# dev1.net
KiCad netlist of a schematic drawn in Altium Designer
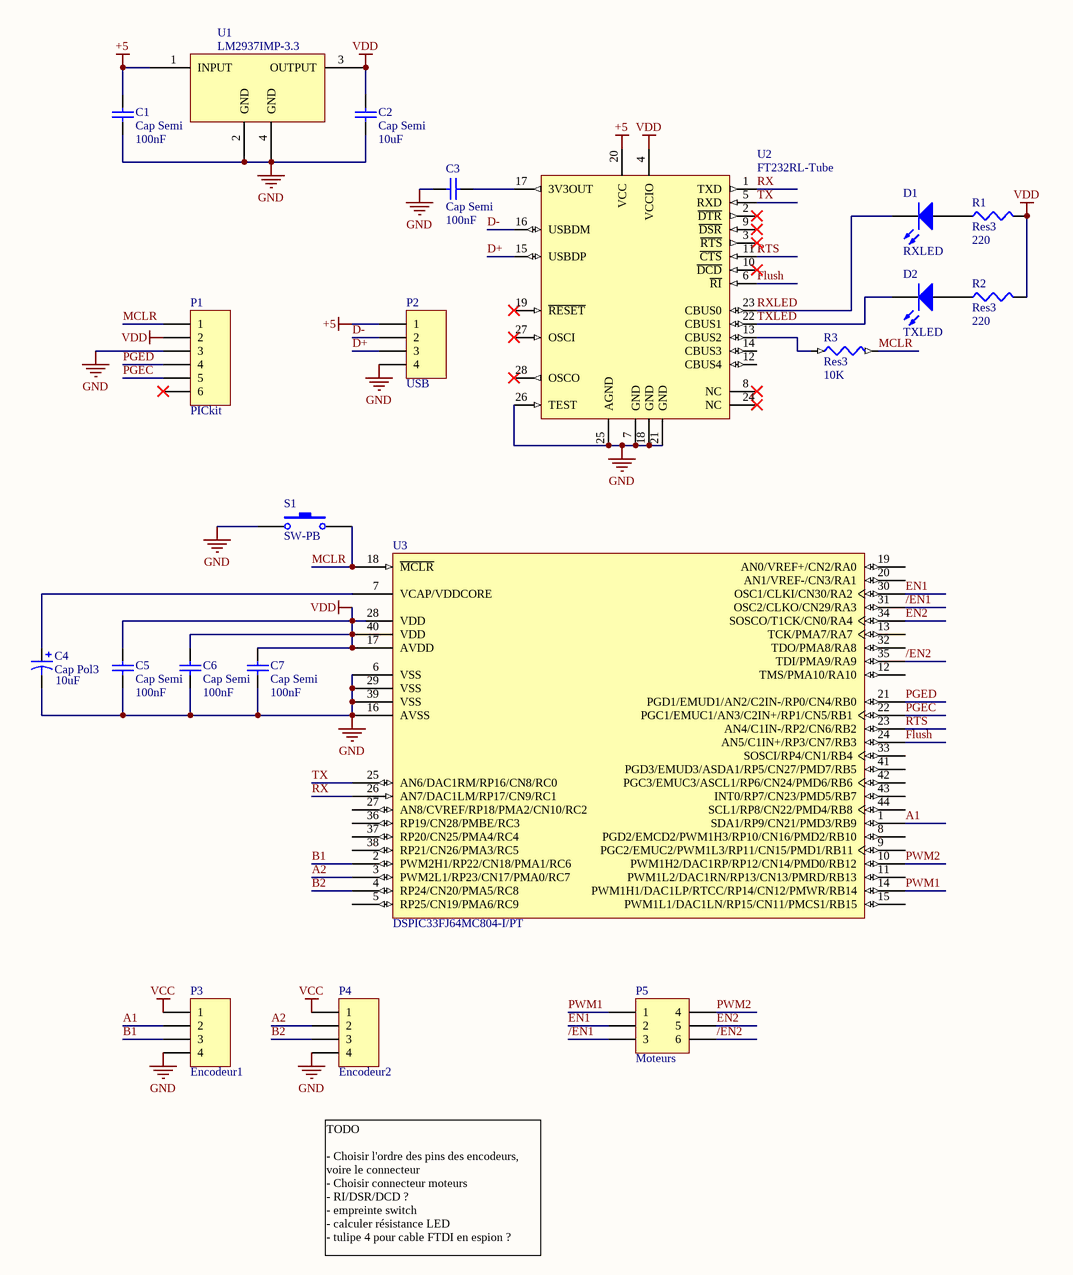
[diagram p0: dev1.SchDoc]

(export (version "E")
  (design (tool "Eeschema 10.0.6"))
  (components
    (comp (ref "C1")
      (value "Cap Semi")
      (footprint "C1206")
      (description "Capacitor (Semiconductor SIM Model)")
      (fields (field (name "ALTIUM_VALUE") "100nF") (field (name "PUBLISHER") "Altium Limited"))
      (libsource (lib "Miscellaneous Devices") (part "Cap Semi"))
    )
    (comp (ref "C2")
      (value "Cap Semi")
      (footprint "C1206")
      (description "Capacitor (Semiconductor SIM Model)")
      (fields (field (name "ALTIUM_VALUE") "10uF") (field (name "PUBLISHER") "Altium Limited"))
      (libsource (lib "Miscellaneous Devices") (part "Cap Semi"))
    )
    (comp (ref "C3")
      (value "Cap Semi")
      (footprint "C1206")
      (description "Capacitor (Semiconductor SIM Model)")
      (fields (field (name "ALTIUM_VALUE") "100nF") (field (name "PUBLISHER") "Altium Limited"))
      (libsource (lib "Miscellaneous Devices") (part "Cap Semi"))
    )
    (comp (ref "C4")
      (value "Cap Pol3")
      (footprint "C0805")
      (description "Polarized Capacitor (Surface Mount)")
      (fields (field (name "ALTIUM_VALUE") "10uF") (field (name "PUBLISHER") "Altium Limited"))
      (libsource (lib "Miscellaneous Devices") (part "Cap Pol3"))
    )
    (comp (ref "C5")
      (value "Cap Semi")
      (footprint "C1206")
      (description "Capacitor (Semiconductor SIM Model)")
      (fields (field (name "ALTIUM_VALUE") "100nF") (field (name "PUBLISHER") "Altium Limited"))
      (libsource (lib "Miscellaneous Devices") (part "Cap Semi"))
    )
    (comp (ref "C6")
      (value "Cap Semi")
      (footprint "C1206")
      (description "Capacitor (Semiconductor SIM Model)")
      (fields (field (name "ALTIUM_VALUE") "100nF") (field (name "PUBLISHER") "Altium Limited"))
      (libsource (lib "Miscellaneous Devices") (part "Cap Semi"))
    )
    (comp (ref "C7")
      (value "Cap Semi")
      (footprint "C1206")
      (description "Capacitor (Semiconductor SIM Model)")
      (fields (field (name "ALTIUM_VALUE") "100nF") (field (name "PUBLISHER") "Altium Limited"))
      (libsource (lib "Miscellaneous Devices") (part "Cap Semi"))
    )
    (comp (ref "D1")
      (value "RXLED")
      (footprint "3.2X1.6X1.1")
      (description "Typical RED, GREEN, YELLOW, AMBER GaAs LED")
      (fields (field (name "PUBLISHER") "Altium Limited"))
      (libsource (lib "Miscellaneous Devices") (part "LED2"))
    )
    (comp (ref "D2")
      (value "TXLED")
      (footprint "3.2X1.6X1.1")
      (description "Typical RED, GREEN, YELLOW, AMBER GaAs LED")
      (fields (field (name "PUBLISHER") "Altium Limited"))
      (libsource (lib "Miscellaneous Devices") (part "LED2"))
    )
    (comp (ref "P1")
      (value "PICkit")
      (footprint "HDR1X6H")
      (description "Header, 6-Pin, Right Angle")
      (fields (field (name "PUBLISHER") "Altium Limited"))
      (libsource (lib "Miscellaneous Connectors") (part "Header 6H"))
    )
    (comp (ref "P2")
      (value "USB")
      (footprint "HDR1X4")
      (description "Header, 4-Pin")
      (fields (field (name "PUBLISHER") "Altium Limited"))
      (libsource (lib "Miscellaneous Connectors") (part "Header 4"))
    )
    (comp (ref "P3")
      (value "Encodeur1")
      (footprint "HDR1X4")
      (description "Header, 4-Pin")
      (fields (field (name "PUBLISHER") "Altium Limited"))
      (libsource (lib "Miscellaneous Connectors") (part "Header 4"))
    )
    (comp (ref "P4")
      (value "Encodeur2")
      (footprint "HDR1X4")
      (description "Header, 4-Pin")
      (fields (field (name "PUBLISHER") "Altium Limited"))
      (libsource (lib "Miscellaneous Connectors") (part "Header 4"))
    )
    (comp (ref "P5")
      (value "Moteurs")
      (footprint "HDR2X3_CEN")
      (description "Header, 3-Pin, Dual row")
      (fields (field (name "PUBLISHER") "Altium Limited"))
      (libsource (lib "Miscellaneous Connectors") (part "Header 3X2A"))
    )
    (comp (ref "R1")
      (value "Res3")
      (footprint "J1-0603")
      (description "Resistor")
      (fields (field (name "ALTIUM_VALUE") "220") (field (name "PUBLISHER") "Altium Limited"))
      (libsource (lib "Miscellaneous Devices") (part "Res3"))
    )
    (comp (ref "R2")
      (value "Res3")
      (footprint "J1-0603")
      (description "Resistor")
      (fields (field (name "ALTIUM_VALUE") "220") (field (name "PUBLISHER") "Altium Limited"))
      (libsource (lib "Miscellaneous Devices") (part "Res3"))
    )
    (comp (ref "R3")
      (value "Res3")
      (footprint "J1-0603")
      (description "Resistor")
      (fields (field (name "ALTIUM_VALUE") "10K") (field (name "PUBLISHER") "Altium Limited"))
      (libsource (lib "Miscellaneous Devices") (part "Res3"))
    )
    (comp (ref "S1")
      (value "SW-PB")
      (footprint "SPST-2")
      (description "Switch")
      (fields (field (name "PUBLISHER") "Altium Limited"))
      (libsource (lib "Miscellaneous Devices") (part "SW-PB"))
    )
    (comp (ref "U1")
      (value "LM2937IMP-3.3")
      (description "500 mA Low Dropout Regulator")
      (libsource (lib "7Robot") (part "LM2937IMP-3.3"))
    )
    (comp (ref "U2")
      (value "FT232RL-Tube")
      (footprint "SSOP-28_N")
      (description "USB UART Asynchronous Serial Data Transfer Chip, SSOP-28, Tube")
      (fields (field (name "PUBLISHER") "Altium Limited"))
      (libsource (lib "FTDI Communication UART") (part "FT232RL-Tube"))
    )
    (comp (ref "U3")
      (value "DSPIC33FJ64MC804-I/PT")
      (footprint "TQFP-PT44_N")
      (fields (field (name "PUBLISHER") "Altium Limited"))
      (libsource (lib "Microchip DSC 16-Bit dsPIC33F") (part "DSPIC33FJ64MC804-I/PT"))
    )
  )
  (nets
    (net (code "1") (name "+5") (class "Default")
      (node (ref "C1") (pin "1") (pinfunction "1_1") (pintype "passive"))
      (node (ref "P2") (pin "1") (pinfunction "1_1") (pintype "passive"))
      (node (ref "U1") (pin "1") (pinfunction "INPUT_1") (pintype "power_in"))
      (node (ref "U2") (pin "20") (pinfunction "VCC_20") (pintype "power_in"))
    )
    (net (code "2") (name "/A1") (class "Default")
      (node (ref "P3") (pin "2") (pinfunction "2_2") (pintype "passive"))
      (node (ref "U3") (pin "1") (pinfunction "SDA1/RP9/CN21/PMD3/RB9_1") (pintype "bidirectional"))
    )
    (net (code "3") (name "/A2") (class "Default")
      (node (ref "P4") (pin "2") (pinfunction "2_2") (pintype "passive"))
      (node (ref "U3") (pin "3") (pinfunction "PWM2L1/RP23/CN17/PMA0/RC7_3") (pintype "bidirectional"))
    )
    (net (code "4") (name "/B1") (class "Default")
      (node (ref "P3") (pin "3") (pinfunction "3_3") (pintype "passive"))
      (node (ref "U3") (pin "2") (pinfunction "PWM2H1/RP22/CN18/PMA1/RC6_2") (pintype "bidirectional"))
    )
    (net (code "5") (name "/B2") (class "Default")
      (node (ref "P4") (pin "3") (pinfunction "3_3") (pintype "passive"))
      (node (ref "U3") (pin "4") (pinfunction "RP24/CN20/PMA5/RC8_4") (pintype "bidirectional"))
    )
    (net (code "6") (name "/D+") (class "Default")
      (node (ref "P2") (pin "3") (pinfunction "3_3") (pintype "passive"))
      (node (ref "U2") (pin "15") (pinfunction "USBDP_15") (pintype "bidirectional"))
    )
    (net (code "7") (name "/D-") (class "Default")
      (node (ref "P2") (pin "2") (pinfunction "2_2") (pintype "passive"))
      (node (ref "U2") (pin "16") (pinfunction "USBDM_16") (pintype "bidirectional"))
    )
    (net (code "8") (name "/EN1") (class "Default")
      (node (ref "P5") (pin "2") (pinfunction "2_2") (pintype "passive"))
      (node (ref "U3") (pin "30") (pinfunction "OSC1/CLKI/CN30/RA2_30") (pintype "bidirectional"))
    )
    (net (code "9") (name "/EN2") (class "Default")
      (node (ref "P5") (pin "5") (pinfunction "5_5") (pintype "passive"))
      (node (ref "U3") (pin "34") (pinfunction "SOSCO/T1CK/CN0/RA4_34") (pintype "bidirectional"))
    )
    (net (code "10") (name "/Flush") (class "Default")
      (node (ref "U2") (pin "6") (pinfunction "~{RI}_6") (pintype "input"))
      (node (ref "U3") (pin "24") (pinfunction "AN5/C1IN+/RP3/CN7/RB3_24") (pintype "bidirectional"))
    )
    (net (code "11") (name "/MCLR") (class "Default")
      (node (ref "P1") (pin "1") (pinfunction "1_1") (pintype "passive"))
      (node (ref "R3") (pin "2") (pinfunction "2_2") (pintype "passive"))
      (node (ref "S1") (pin "2") (pinfunction "2_2") (pintype "passive"))
      (node (ref "U3") (pin "18") (pinfunction "~{MCLR}_18") (pintype "input"))
    )
    (net (code "12") (name "/PGEC") (class "Default")
      (node (ref "P1") (pin "5") (pinfunction "5_5") (pintype "passive"))
      (node (ref "U3") (pin "22") (pinfunction "PGC1/EMUC1/AN3/C2IN+/RP1/CN5/RB1_22") (pintype "bidirectional"))
    )
    (net (code "13") (name "/PGED") (class "Default")
      (node (ref "P1") (pin "4") (pinfunction "4_4") (pintype "passive"))
      (node (ref "U3") (pin "21") (pinfunction "PGD1/EMUD1/AN2/C2IN-/RP0/CN4/RB0_21") (pintype "bidirectional"))
    )
    (net (code "14") (name "/PWM1") (class "Default")
      (node (ref "P5") (pin "1") (pinfunction "1_1") (pintype "passive"))
      (node (ref "U3") (pin "14") (pinfunction "PWM1H1/DAC1LP/RTCC/RP14/CN12/PMWR/RB14_14") (pintype "bidirectional"))
    )
    (net (code "15") (name "/PWM2") (class "Default")
      (node (ref "P5") (pin "4") (pinfunction "4_4") (pintype "passive"))
      (node (ref "U3") (pin "10") (pinfunction "PWM1H2/DAC1RP/RP12/CN14/PMD0/RB12_10") (pintype "bidirectional"))
    )
    (net (code "16") (name "/RTS") (class "Default")
      (node (ref "U2") (pin "11") (pinfunction "~{CTS}_11") (pintype "input"))
      (node (ref "U3") (pin "23") (pinfunction "AN4/C1IN-/RP2/CN6/RB2_23") (pintype "bidirectional"))
    )
    (net (code "17") (name "/RX") (class "Default")
      (node (ref "U2") (pin "1") (pinfunction "TXD_1") (pintype "output"))
      (node (ref "U3") (pin "26") (pinfunction "AN7/DAC1LM/RP17/CN9/RC1_26") (pintype "input"))
    )
    (net (code "18") (name "/RXLED") (class "Default")
      (node (ref "D1") (pin "2") (pinfunction "K_2") (pintype "passive"))
      (node (ref "U2") (pin "23") (pinfunction "CBUS0_23") (pintype "bidirectional"))
    )
    (net (code "19") (name "/TX") (class "Default")
      (node (ref "U2") (pin "5") (pinfunction "RXD_5") (pintype "input"))
      (node (ref "U3") (pin "25") (pinfunction "AN6/DAC1RM/RP16/CN8/RC0_25") (pintype "bidirectional"))
    )
    (net (code "20") (name "/TXLED") (class "Default")
      (node (ref "D2") (pin "2") (pinfunction "K_2") (pintype "passive"))
      (node (ref "U2") (pin "22") (pinfunction "CBUS1_22") (pintype "bidirectional"))
    )
    (net (code "21") (name "/{slash}EN1") (class "Default")
      (node (ref "P5") (pin "3") (pinfunction "3_3") (pintype "passive"))
      (node (ref "U3") (pin "31") (pinfunction "OSC2/CLKO/CN29/RA3_31") (pintype "bidirectional"))
    )
    (net (code "22") (name "/{slash}EN2") (class "Default")
      (node (ref "P5") (pin "6") (pinfunction "6_6") (pintype "passive"))
      (node (ref "U3") (pin "35") (pinfunction "TDI/PMA9/RA9_35") (pintype "bidirectional"))
    )
    (net (code "23") (name "GND") (class "Default")
      (node (ref "C1") (pin "2") (pinfunction "2_2") (pintype "passive"))
      (node (ref "C2") (pin "2") (pinfunction "2_2") (pintype "passive"))
      (node (ref "C3") (pin "1") (pinfunction "1_1") (pintype "passive"))
      (node (ref "C4") (pin "2") (pinfunction "2_2") (pintype "passive"))
      (node (ref "C5") (pin "2") (pinfunction "2_2") (pintype "passive"))
      (node (ref "C6") (pin "2") (pinfunction "2_2") (pintype "passive"))
      (node (ref "C7") (pin "2") (pinfunction "2_2") (pintype "passive"))
      (node (ref "P1") (pin "3") (pinfunction "3_3") (pintype "passive"))
      (node (ref "P2") (pin "4") (pinfunction "4_4") (pintype "passive"))
      (node (ref "P3") (pin "4") (pinfunction "4_4") (pintype "passive"))
      (node (ref "P4") (pin "4") (pinfunction "4_4") (pintype "passive"))
      (node (ref "S1") (pin "1") (pinfunction "1_1") (pintype "passive"))
      (node (ref "U1") (pin "2") (pinfunction "GND_2") (pintype "power_in"))
      (node (ref "U1") (pin "4") (pinfunction "GND_4") (pintype "power_in"))
      (node (ref "U2") (pin "18") (pinfunction "GND_18") (pintype "power_in"))
      (node (ref "U2") (pin "21") (pinfunction "GND_21") (pintype "power_in"))
      (node (ref "U2") (pin "25") (pinfunction "AGND_25") (pintype "power_in"))
      (node (ref "U2") (pin "26") (pinfunction "TEST_26") (pintype "input"))
      (node (ref "U2") (pin "7") (pinfunction "GND_7") (pintype "power_in"))
      (node (ref "U3") (pin "16") (pinfunction "AVSS_16") (pintype "power_in"))
      (node (ref "U3") (pin "29") (pinfunction "VSS_29") (pintype "power_in"))
      (node (ref "U3") (pin "39") (pinfunction "VSS_39") (pintype "power_in"))
      (node (ref "U3") (pin "6") (pinfunction "VSS_6") (pintype "power_in"))
    )
    (net (code "24") (name "Net-(D1-A)") (class "Default")
      (node (ref "D1") (pin "1") (pinfunction "A_1") (pintype "passive"))
      (node (ref "R1") (pin "1") (pinfunction "1_1") (pintype "passive"))
    )
    (net (code "25") (name "Net-(D2-A)") (class "Default")
      (node (ref "D2") (pin "1") (pinfunction "A_1") (pintype "passive"))
      (node (ref "R2") (pin "1") (pinfunction "1_1") (pintype "passive"))
    )
    (net (code "26") (name "Net-(U2-3V3OUT)") (class "Default")
      (node (ref "C3") (pin "2") (pinfunction "2_2") (pintype "passive"))
      (node (ref "U2") (pin "17") (pinfunction "3V3OUT_17") (pintype "output"))
    )
    (net (code "27") (name "Net-(U2-CBUS2)") (class "Default")
      (node (ref "R3") (pin "1") (pinfunction "1_1") (pintype "passive"))
      (node (ref "U2") (pin "13") (pinfunction "CBUS2_13") (pintype "bidirectional"))
    )
    (net (code "28") (name "Net-(U3-VCAP{slash}VDDCORE)") (class "Default")
      (node (ref "C4") (pin "1") (pinfunction "1_1") (pintype "passive"))
      (node (ref "U3") (pin "7") (pinfunction "VCAP/VDDCORE_7") (pintype "power_in"))
    )
    (net (code "29") (name "VCC") (class "Default")
      (node (ref "P3") (pin "1") (pinfunction "1_1") (pintype "passive"))
      (node (ref "P4") (pin "1") (pinfunction "1_1") (pintype "passive"))
    )
    (net (code "30") (name "VDD") (class "Default")
      (node (ref "C2") (pin "1") (pinfunction "1_1") (pintype "passive"))
      (node (ref "C5") (pin "1") (pinfunction "1_1") (pintype "passive"))
      (node (ref "C6") (pin "1") (pinfunction "1_1") (pintype "passive"))
      (node (ref "C7") (pin "1") (pinfunction "1_1") (pintype "passive"))
      (node (ref "P1") (pin "2") (pinfunction "2_2") (pintype "passive"))
      (node (ref "R1") (pin "2") (pinfunction "2_2") (pintype "passive"))
      (node (ref "R2") (pin "2") (pinfunction "2_2") (pintype "passive"))
      (node (ref "U1") (pin "3") (pinfunction "OUTPUT_3") (pintype "power_in"))
      (node (ref "U2") (pin "4") (pinfunction "VCCIO_4") (pintype "power_in"))
      (node (ref "U3") (pin "17") (pinfunction "AVDD_17") (pintype "power_in"))
      (node (ref "U3") (pin "28") (pinfunction "VDD_28") (pintype "power_in"))
      (node (ref "U3") (pin "40") (pinfunction "VDD_40") (pintype "power_in"))
    )
    (net (code "31") (name "unconnected-(P1-Pad6)") (class "Default")
      (node (ref "P1") (pin "6") (pinfunction "6_6") (pintype "passive+no_connect"))
    )
    (net (code "32") (name "unconnected-(U2-CBUS3-Pad14)") (class "Default")
      (node (ref "U2") (pin "14") (pinfunction "CBUS3_14") (pintype "bidirectional"))
    )
    (net (code "33") (name "unconnected-(U2-CBUS4-Pad12)") (class "Default")
      (node (ref "U2") (pin "12") (pinfunction "CBUS4_12") (pintype "bidirectional"))
    )
    (net (code "34") (name "unconnected-(U2-NC-Pad8)") (class "Default")
      (node (ref "U2") (pin "8") (pinfunction "NC_8") (pintype "passive+no_connect"))
    )
    (net (code "35") (name "unconnected-(U2-NC-Pad24)") (class "Default")
      (node (ref "U2") (pin "24") (pinfunction "NC_24") (pintype "passive+no_connect"))
    )
    (net (code "36") (name "unconnected-(U2-OSCI-Pad27)") (class "Default")
      (node (ref "U2") (pin "27") (pinfunction "OSCI_27") (pintype "input+no_connect"))
    )
    (net (code "37") (name "unconnected-(U2-OSCO-Pad28)") (class "Default")
      (node (ref "U2") (pin "28") (pinfunction "OSCO_28") (pintype "output+no_connect"))
    )
    (net (code "38") (name "unconnected-(U2-~{DCD}-Pad10)") (class "Default")
      (node (ref "U2") (pin "10") (pinfunction "~{DCD}_10") (pintype "input+no_connect"))
    )
    (net (code "39") (name "unconnected-(U2-~{DSR}-Pad9)") (class "Default")
      (node (ref "U2") (pin "9") (pinfunction "~{DSR}_9") (pintype "input+no_connect"))
    )
    (net (code "40") (name "unconnected-(U2-~{DTR}-Pad2)") (class "Default")
      (node (ref "U2") (pin "2") (pinfunction "~{DTR}_2") (pintype "output+no_connect"))
    )
    (net (code "41") (name "unconnected-(U2-~{RESET}-Pad19)") (class "Default")
      (node (ref "U2") (pin "19") (pinfunction "~{RESET}_19") (pintype "input+no_connect"))
    )
    (net (code "42") (name "unconnected-(U2-~{RTS}-Pad3)") (class "Default")
      (node (ref "U2") (pin "3") (pinfunction "~{RTS}_3") (pintype "output+no_connect"))
    )
    (net (code "43") (name "unconnected-(U3-AN0{slash}VREF+{slash}CN2{slash}RA0-Pad19)") (class "Default")
      (node (ref "U3") (pin "19") (pinfunction "AN0/VREF+/CN2/RA0_19") (pintype "bidirectional"))
    )
    (net (code "44") (name "unconnected-(U3-AN1{slash}VREF-{slash}CN3{slash}RA1-Pad20)") (class "Default")
      (node (ref "U3") (pin "20") (pinfunction "AN1/VREF-/CN3/RA1_20") (pintype "bidirectional"))
    )
    (net (code "45") (name "unconnected-(U3-AN8{slash}CVREF{slash}RP18{slash}PMA2{slash}CN10{slash}RC2-Pad27)") (class "Default")
      (node (ref "U3") (pin "27") (pinfunction "AN8/CVREF/RP18/PMA2/CN10/RC2_27") (pintype "bidirectional"))
    )
    (net (code "46") (name "unconnected-(U3-INT0{slash}RP7{slash}CN23{slash}PMD5{slash}RB7-Pad43)") (class "Default")
      (node (ref "U3") (pin "43") (pinfunction "INT0/RP7/CN23/PMD5/RB7_43") (pintype "bidirectional"))
    )
    (net (code "47") (name "unconnected-(U3-PGC2{slash}EMUC2{slash}PWM1L3{slash}RP11{slash}CN15{slash}PMD1{slash}RB11-Pad9)") (class "Default")
      (node (ref "U3") (pin "9") (pinfunction "PGC2/EMUC2/PWM1L3/RP11/CN15/PMD1/RB11_9") (pintype "bidirectional"))
    )
    (net (code "48") (name "unconnected-(U3-PGC3{slash}EMUC3{slash}ASCL1{slash}RP6{slash}CN24{slash}PMD6{slash}RB6-Pad42)") (class "Default")
      (node (ref "U3") (pin "42") (pinfunction "PGC3/EMUC3/ASCL1/RP6/CN24/PMD6/RB6_42") (pintype "bidirectional"))
    )
    (net (code "49") (name "unconnected-(U3-PGD2{slash}EMCD2{slash}PWM1H3{slash}RP10{slash}CN16{slash}PMD2{slash}RB10-Pad8)") (class "Default")
      (node (ref "U3") (pin "8") (pinfunction "PGD2/EMCD2/PWM1H3/RP10/CN16/PMD2/RB10_8") (pintype "bidirectional"))
    )
    (net (code "50") (name "unconnected-(U3-PGD3{slash}EMUD3{slash}ASDA1{slash}RP5{slash}CN27{slash}PMD7{slash}RB5-Pad41)") (class "Default")
      (node (ref "U3") (pin "41") (pinfunction "PGD3/EMUD3/ASDA1/RP5/CN27/PMD7/RB5_41") (pintype "bidirectional"))
    )
    (net (code "51") (name "unconnected-(U3-PWM1L1{slash}DAC1LN{slash}RP15{slash}CN11{slash}PMCS1{slash}RB15-Pad15)") (class "Default")
      (node (ref "U3") (pin "15") (pinfunction "PWM1L1/DAC1LN/RP15/CN11/PMCS1/RB15_15") (pintype "bidirectional"))
    )
    (net (code "52") (name "unconnected-(U3-PWM1L2{slash}DAC1RN{slash}RP13{slash}CN13{slash}PMRD{slash}RB13-Pad11)") (class "Default")
      (node (ref "U3") (pin "11") (pinfunction "PWM1L2/DAC1RN/RP13/CN13/PMRD/RB13_11") (pintype "bidirectional"))
    )
    (net (code "53") (name "unconnected-(U3-RP19{slash}CN28{slash}PMBE{slash}RC3-Pad36)") (class "Default")
      (node (ref "U3") (pin "36") (pinfunction "RP19/CN28/PMBE/RC3_36") (pintype "bidirectional"))
    )
    (net (code "54") (name "unconnected-(U3-RP20{slash}CN25{slash}PMA4{slash}RC4-Pad37)") (class "Default")
      (node (ref "U3") (pin "37") (pinfunction "RP20/CN25/PMA4/RC4_37") (pintype "bidirectional"))
    )
    (net (code "55") (name "unconnected-(U3-RP21{slash}CN26{slash}PMA3{slash}RC5-Pad38)") (class "Default")
      (node (ref "U3") (pin "38") (pinfunction "RP21/CN26/PMA3/RC5_38") (pintype "bidirectional"))
    )
    (net (code "56") (name "unconnected-(U3-RP25{slash}CN19{slash}PMA6{slash}RC9-Pad5)") (class "Default")
      (node (ref "U3") (pin "5") (pinfunction "RP25/CN19/PMA6/RC9_5") (pintype "bidirectional"))
    )
    (net (code "57") (name "unconnected-(U3-SCL1{slash}RP8{slash}CN22{slash}PMD4{slash}RB8-Pad44)") (class "Default")
      (node (ref "U3") (pin "44") (pinfunction "SCL1/RP8/CN22/PMD4/RB8_44") (pintype "bidirectional"))
    )
    (net (code "58") (name "unconnected-(U3-SOSCI{slash}RP4{slash}CN1{slash}RB4-Pad33)") (class "Default")
      (node (ref "U3") (pin "33") (pinfunction "SOSCI/RP4/CN1/RB4_33") (pintype "bidirectional"))
    )
    (net (code "59") (name "unconnected-(U3-TCK{slash}PMA7{slash}RA7-Pad13)") (class "Default")
      (node (ref "U3") (pin "13") (pinfunction "TCK/PMA7/RA7_13") (pintype "bidirectional"))
    )
    (net (code "60") (name "unconnected-(U3-TDO{slash}PMA8{slash}RA8-Pad32)") (class "Default")
      (node (ref "U3") (pin "32") (pinfunction "TDO/PMA8/RA8_32") (pintype "bidirectional"))
    )
    (net (code "61") (name "unconnected-(U3-TMS{slash}PMA10{slash}RA10-Pad12)") (class "Default")
      (node (ref "U3") (pin "12") (pinfunction "TMS/PMA10/RA10_12") (pintype "bidirectional"))
    )
  )
)
